# adc.net
KiCad netlist of a schematic drawn in Altium Designer
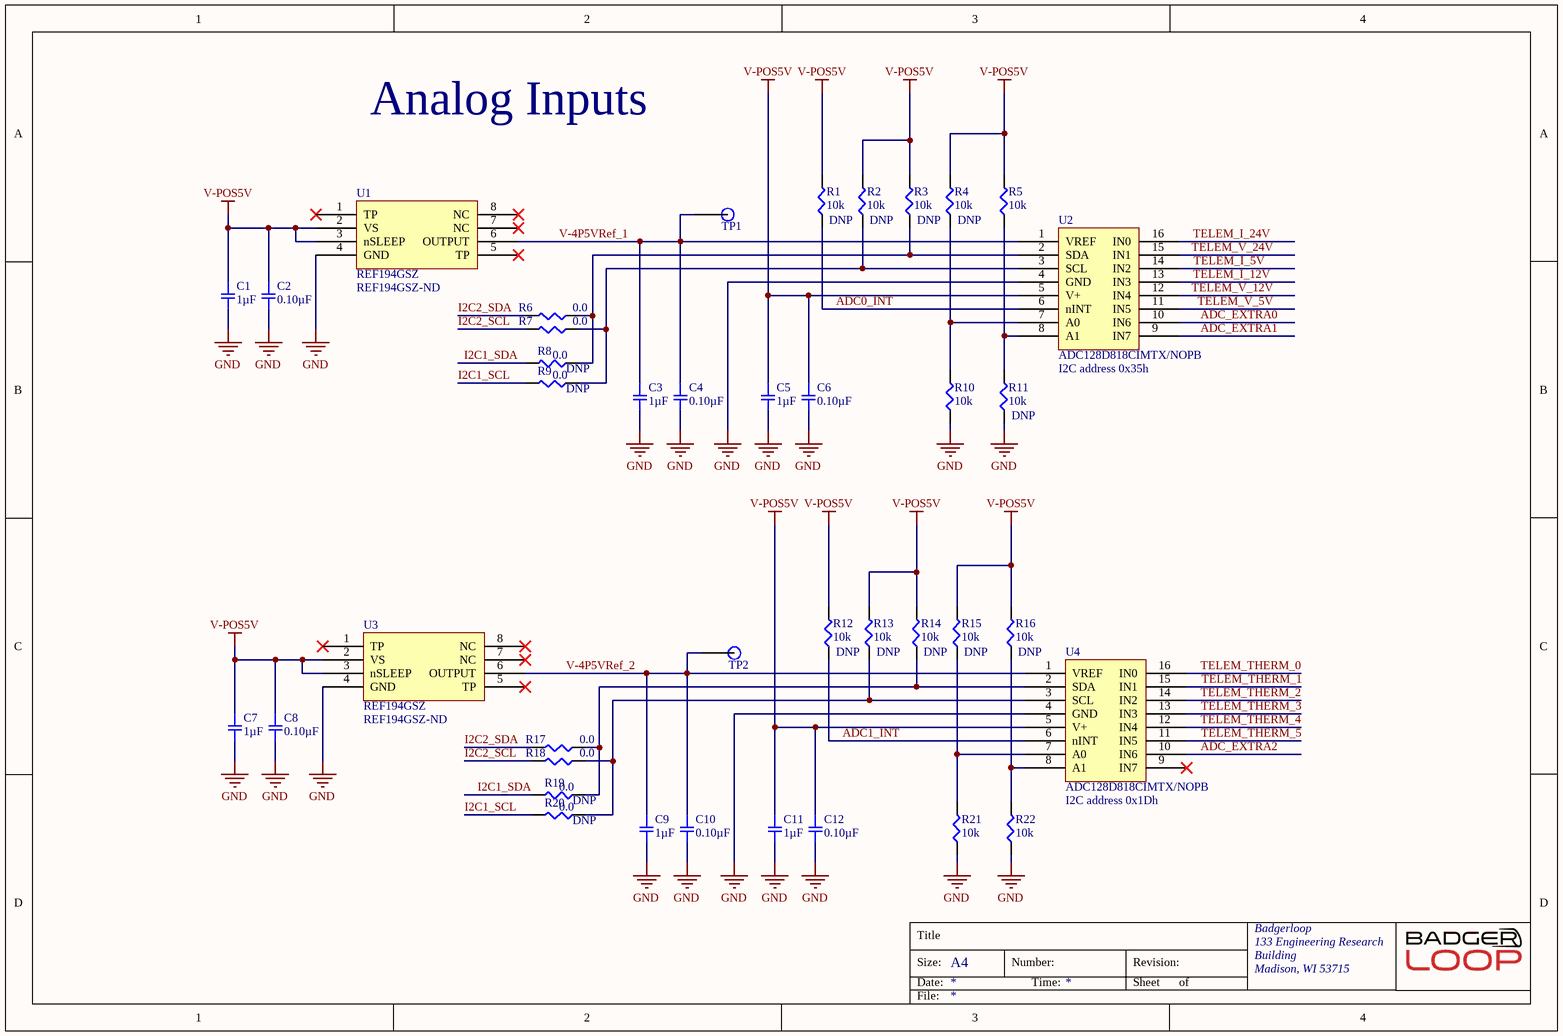
[diagram p0: adc.SchDoc]

(export (version "E")
  (design (tool "Eeschema 10.0.6"))
  (components
    (comp (ref "C1")
      (value "1µF")
      (footprint "SMD-0805C")
      (description "CAP CER 1UF 50V X7R 0805")
      (fields
        (field (name "DIGI-KEY PART NUMBER") "490-4736-1-ND")
        (field (name "PART NUMBER") "GRM21BR71H105KA12L")
      )
      (libsource (lib "capacitors") (part "GRM21BR71H105KA12L"))
    )
    (comp (ref "C2")
      (value "0.10µF")
      (footprint "SMD-0805C")
      (description "CAP CER 0.1UF 50V X7R 0805")
      (fields
        (field (name "DIGI-KEY PART NUMBER") "490-11955-1-ND")
        (field (name "PART NUMBER") "GCD21BR71H104KA01L")
      )
      (libsource (lib "capacitors") (part "GCD21BR71H104KA01L"))
    )
    (comp (ref "C3")
      (value "1µF")
      (footprint "SMD-0805C")
      (description "CAP CER 1UF 50V X7R 0805")
      (fields
        (field (name "DIGI-KEY PART NUMBER") "490-4736-1-ND")
        (field (name "PART NUMBER") "GRM21BR71H105KA12L")
      )
      (libsource (lib "capacitors") (part "GRM21BR71H105KA12L"))
    )
    (comp (ref "C4")
      (value "0.10µF")
      (footprint "SMD-0805C")
      (description "CAP CER 0.1UF 50V X7R 0805")
      (fields
        (field (name "DIGI-KEY PART NUMBER") "490-11955-1-ND")
        (field (name "PART NUMBER") "GCD21BR71H104KA01L")
      )
      (libsource (lib "capacitors") (part "GCD21BR71H104KA01L"))
    )
    (comp (ref "C5")
      (value "1µF")
      (footprint "SMD-0805C")
      (description "CAP CER 1UF 50V X7R 0805")
      (fields
        (field (name "DIGI-KEY PART NUMBER") "490-4736-1-ND")
        (field (name "PART NUMBER") "GRM21BR71H105KA12L")
      )
      (libsource (lib "capacitors") (part "GRM21BR71H105KA12L"))
    )
    (comp (ref "C6")
      (value "0.10µF")
      (footprint "SMD-0805C")
      (description "CAP CER 0.1UF 50V X7R 0805")
      (fields
        (field (name "DIGI-KEY PART NUMBER") "490-11955-1-ND")
        (field (name "PART NUMBER") "GCD21BR71H104KA01L")
      )
      (libsource (lib "capacitors") (part "GCD21BR71H104KA01L"))
    )
    (comp (ref "C7")
      (value "1µF")
      (footprint "SMD-0805C")
      (description "CAP CER 1UF 50V X7R 0805")
      (fields
        (field (name "DIGI-KEY PART NUMBER") "490-4736-1-ND")
        (field (name "PART NUMBER") "GRM21BR71H105KA12L")
      )
      (libsource (lib "capacitors") (part "GRM21BR71H105KA12L"))
    )
    (comp (ref "C8")
      (value "0.10µF")
      (footprint "SMD-0805C")
      (description "CAP CER 0.1UF 50V X7R 0805")
      (fields
        (field (name "DIGI-KEY PART NUMBER") "490-11955-1-ND")
        (field (name "PART NUMBER") "GCD21BR71H104KA01L")
      )
      (libsource (lib "capacitors") (part "GCD21BR71H104KA01L"))
    )
    (comp (ref "C9")
      (value "1µF")
      (footprint "SMD-0805C")
      (description "CAP CER 1UF 50V X7R 0805")
      (fields
        (field (name "DIGI-KEY PART NUMBER") "490-4736-1-ND")
        (field (name "PART NUMBER") "GRM21BR71H105KA12L")
      )
      (libsource (lib "capacitors") (part "GRM21BR71H105KA12L"))
    )
    (comp (ref "C10")
      (value "0.10µF")
      (footprint "SMD-0805C")
      (description "CAP CER 0.1UF 50V X7R 0805")
      (fields
        (field (name "DIGI-KEY PART NUMBER") "490-11955-1-ND")
        (field (name "PART NUMBER") "GCD21BR71H104KA01L")
      )
      (libsource (lib "capacitors") (part "GCD21BR71H104KA01L"))
    )
    (comp (ref "C11")
      (value "1µF")
      (footprint "SMD-0805C")
      (description "CAP CER 1UF 50V X7R 0805")
      (fields
        (field (name "DIGI-KEY PART NUMBER") "490-4736-1-ND")
        (field (name "PART NUMBER") "GRM21BR71H105KA12L")
      )
      (libsource (lib "capacitors") (part "GRM21BR71H105KA12L"))
    )
    (comp (ref "C12")
      (value "0.10µF")
      (footprint "SMD-0805C")
      (description "CAP CER 0.1UF 50V X7R 0805")
      (fields
        (field (name "DIGI-KEY PART NUMBER") "490-11955-1-ND")
        (field (name "PART NUMBER") "GCD21BR71H104KA01L")
      )
      (libsource (lib "capacitors") (part "GCD21BR71H104KA01L"))
    )
    (comp (ref "R1")
      (value "10k")
      (footprint "SMD-0805-RES")
      (description "RES SMD 10K OHM 5% 1/2W 0805")
      (fields
        (field (name "PART NUMBER") "ERJ-P06J103V")
        (field (name "DIGI-KEY PART NUMBER") "P10KADCT-ND")
        (field (name "DNP") "DNP")
      )
      (libsource (lib "resistors") (part "ERJ-P06J103V"))
    )
    (comp (ref "R2")
      (value "10k")
      (footprint "SMD-0805-RES")
      (description "RES SMD 10K OHM 5% 1/2W 0805")
      (fields
        (field (name "PART NUMBER") "ERJ-P06J103V")
        (field (name "DIGI-KEY PART NUMBER") "P10KADCT-ND")
        (field (name "DNP") "DNP")
      )
      (libsource (lib "resistors") (part "ERJ-P06J103V"))
    )
    (comp (ref "R3")
      (value "10k")
      (footprint "SMD-0805-RES")
      (description "RES SMD 10K OHM 5% 1/2W 0805")
      (fields
        (field (name "PART NUMBER") "ERJ-P06J103V")
        (field (name "DIGI-KEY PART NUMBER") "P10KADCT-ND")
        (field (name "DNP") "DNP")
      )
      (libsource (lib "resistors") (part "ERJ-P06J103V"))
    )
    (comp (ref "R4")
      (value "10k")
      (footprint "SMD-0805-RES")
      (description "RES SMD 10K OHM 5% 1/2W 0805")
      (fields
        (field (name "PART NUMBER") "ERJ-P06J103V")
        (field (name "DIGI-KEY PART NUMBER") "P10KADCT-ND")
        (field (name "DNP") "DNP")
      )
      (libsource (lib "resistors") (part "ERJ-P06J103V"))
    )
    (comp (ref "R5")
      (value "10k")
      (footprint "SMD-0805-RES")
      (description "RES SMD 10K OHM 5% 1/2W 0805")
      (fields (field (name "PART NUMBER") "ERJ-P06J103V") (field (name "DIGI-KEY PART NUMBER") "P10KADCT-ND"))
      (libsource (lib "resistors") (part "ERJ-P06J103V"))
    )
    (comp (ref "R6")
      (value "0.0")
      (footprint "SMD-0805-RES")
      (description "RES SMD 0.0 OHM JUMPER 1/8W 0805")
      (fields (field (name "PART NUMBER") "ERJ-6GEY0R00V") (field (name "DIGI-KEY PART NUMBER") "P0.0ACT-ND"))
      (libsource (lib "resistors") (part "ERJ-6GEY0R00V"))
    )
    (comp (ref "R7")
      (value "0.0")
      (footprint "SMD-0805-RES")
      (description "RES SMD 0.0 OHM JUMPER 1/8W 0805")
      (fields (field (name "PART NUMBER") "ERJ-6GEY0R00V") (field (name "DIGI-KEY PART NUMBER") "P0.0ACT-ND"))
      (libsource (lib "resistors") (part "ERJ-6GEY0R00V"))
    )
    (comp (ref "R8")
      (value "0.0")
      (footprint "SMD-0805-RES")
      (description "RES SMD 0.0 OHM JUMPER 1/8W 0805")
      (fields
        (field (name "PART NUMBER") "ERJ-6GEY0R00V")
        (field (name "DIGI-KEY PART NUMBER") "P0.0ACT-ND")
        (field (name "DNP") "DNP")
      )
      (libsource (lib "resistors") (part "ERJ-6GEY0R00V"))
    )
    (comp (ref "R9")
      (value "0.0")
      (footprint "SMD-0805-RES")
      (description "RES SMD 0.0 OHM JUMPER 1/8W 0805")
      (fields
        (field (name "PART NUMBER") "ERJ-6GEY0R00V")
        (field (name "DIGI-KEY PART NUMBER") "P0.0ACT-ND")
        (field (name "DNP") "DNP")
      )
      (libsource (lib "resistors") (part "ERJ-6GEY0R00V"))
    )
    (comp (ref "R10")
      (value "10k")
      (footprint "SMD-0805-RES")
      (description "RES SMD 10K OHM 5% 1/2W 0805")
      (fields (field (name "PART NUMBER") "ERJ-P06J103V") (field (name "DIGI-KEY PART NUMBER") "P10KADCT-ND"))
      (libsource (lib "resistors") (part "ERJ-P06J103V"))
    )
    (comp (ref "R11")
      (value "10k")
      (footprint "SMD-0805-RES")
      (description "RES SMD 10K OHM 5% 1/2W 0805")
      (fields
        (field (name "PART NUMBER") "ERJ-P06J103V")
        (field (name "DIGI-KEY PART NUMBER") "P10KADCT-ND")
        (field (name "DNP") "DNP")
      )
      (libsource (lib "resistors") (part "ERJ-P06J103V"))
    )
    (comp (ref "R12")
      (value "10k")
      (footprint "SMD-0805-RES")
      (description "RES SMD 10K OHM 5% 1/2W 0805")
      (fields
        (field (name "PART NUMBER") "ERJ-P06J103V")
        (field (name "DIGI-KEY PART NUMBER") "P10KADCT-ND")
        (field (name "DNP") "DNP")
      )
      (libsource (lib "resistors") (part "ERJ-P06J103V"))
    )
    (comp (ref "R13")
      (value "10k")
      (footprint "SMD-0805-RES")
      (description "RES SMD 10K OHM 5% 1/2W 0805")
      (fields
        (field (name "PART NUMBER") "ERJ-P06J103V")
        (field (name "DIGI-KEY PART NUMBER") "P10KADCT-ND")
        (field (name "DNP") "DNP")
      )
      (libsource (lib "resistors") (part "ERJ-P06J103V"))
    )
    (comp (ref "R14")
      (value "10k")
      (footprint "SMD-0805-RES")
      (description "RES SMD 10K OHM 5% 1/2W 0805")
      (fields
        (field (name "PART NUMBER") "ERJ-P06J103V")
        (field (name "DIGI-KEY PART NUMBER") "P10KADCT-ND")
        (field (name "DNP") "DNP")
      )
      (libsource (lib "resistors") (part "ERJ-P06J103V"))
    )
    (comp (ref "R15")
      (value "10k")
      (footprint "SMD-0805-RES")
      (description "RES SMD 10K OHM 5% 1/2W 0805")
      (fields
        (field (name "PART NUMBER") "ERJ-P06J103V")
        (field (name "DIGI-KEY PART NUMBER") "P10KADCT-ND")
        (field (name "DNP") "DNP")
      )
      (libsource (lib "resistors") (part "ERJ-P06J103V"))
    )
    (comp (ref "R16")
      (value "10k")
      (footprint "SMD-0805-RES")
      (description "RES SMD 10K OHM 5% 1/2W 0805")
      (fields
        (field (name "PART NUMBER") "ERJ-P06J103V")
        (field (name "DIGI-KEY PART NUMBER") "P10KADCT-ND")
        (field (name "DNP") "DNP")
      )
      (libsource (lib "resistors") (part "ERJ-P06J103V"))
    )
    (comp (ref "R17")
      (value "0.0")
      (footprint "SMD-0805-RES")
      (description "RES SMD 0.0 OHM JUMPER 1/8W 0805")
      (fields (field (name "PART NUMBER") "ERJ-6GEY0R00V") (field (name "DIGI-KEY PART NUMBER") "P0.0ACT-ND"))
      (libsource (lib "resistors") (part "ERJ-6GEY0R00V"))
    )
    (comp (ref "R18")
      (value "0.0")
      (footprint "SMD-0805-RES")
      (description "RES SMD 0.0 OHM JUMPER 1/8W 0805")
      (fields (field (name "PART NUMBER") "ERJ-6GEY0R00V") (field (name "DIGI-KEY PART NUMBER") "P0.0ACT-ND"))
      (libsource (lib "resistors") (part "ERJ-6GEY0R00V"))
    )
    (comp (ref "R19")
      (value "0.0")
      (footprint "SMD-0805-RES")
      (description "RES SMD 0.0 OHM JUMPER 1/8W 0805")
      (fields
        (field (name "PART NUMBER") "ERJ-6GEY0R00V")
        (field (name "DIGI-KEY PART NUMBER") "P0.0ACT-ND")
        (field (name "DNP") "DNP")
      )
      (libsource (lib "resistors") (part "ERJ-6GEY0R00V"))
    )
    (comp (ref "R20")
      (value "0.0")
      (footprint "SMD-0805-RES")
      (description "RES SMD 0.0 OHM JUMPER 1/8W 0805")
      (fields
        (field (name "PART NUMBER") "ERJ-6GEY0R00V")
        (field (name "DIGI-KEY PART NUMBER") "P0.0ACT-ND")
        (field (name "DNP") "DNP")
      )
      (libsource (lib "resistors") (part "ERJ-6GEY0R00V"))
    )
    (comp (ref "R21")
      (value "10k")
      (footprint "SMD-0805-RES")
      (description "RES SMD 10K OHM 5% 1/2W 0805")
      (fields (field (name "PART NUMBER") "ERJ-P06J103V") (field (name "DIGI-KEY PART NUMBER") "P10KADCT-ND"))
      (libsource (lib "resistors") (part "ERJ-P06J103V"))
    )
    (comp (ref "R22")
      (value "10k")
      (footprint "SMD-0805-RES")
      (description "RES SMD 10K OHM 5% 1/2W 0805")
      (fields (field (name "PART NUMBER") "ERJ-P06J103V") (field (name "DIGI-KEY PART NUMBER") "P10KADCT-ND"))
      (libsource (lib "resistors") (part "ERJ-P06J103V"))
    )
    (comp (ref "TP1")
      (value "TP")
      (footprint "Test Point")
      (description "SMD TEST POINT")
      (libsource (lib "misc") (part "TP"))
    )
    (comp (ref "TP2")
      (value "TP")
      (footprint "Test Point")
      (description "SMD TEST POINT")
      (libsource (lib "misc") (part "TP"))
    )
    (comp (ref "U1")
      (value "REF194GSZ")
      (footprint "SOP127P600X175-8N")
      (description "IC VREF SERIES 4.5V 8SOIC")
      (fields
        (field (name "MANUFACTURER") "Analog Devices")
        (field (name "SUPPLIER PART NUMBER 1") "REF194GSZ-ND")
      )
      (libsource (lib "ic") (part "REF194GSZ"))
    )
    (comp (ref "U2")
      (value "ADC128D818CIMTX/NOPB")
      (footprint "TSOP65P660X120-16N")
      (description "Analog to Digital Converters - ADC")
      (fields (field (name "MANUFACTURER") "TI National Semiconductor"))
      (libsource (lib "ic") (part "ADC128D818CIMTX/NOPB"))
    )
    (comp (ref "U3")
      (value "REF194GSZ")
      (footprint "SOP127P600X175-8N")
      (description "IC VREF SERIES 4.5V 8SOIC")
      (fields
        (field (name "MANUFACTURER") "Analog Devices")
        (field (name "SUPPLIER PART NUMBER 1") "REF194GSZ-ND")
      )
      (libsource (lib "ic") (part "REF194GSZ"))
    )
    (comp (ref "U4")
      (value "ADC128D818CIMTX/NOPB")
      (footprint "TSOP65P660X120-16N")
      (description "Analog to Digital Converters - ADC")
      (fields (field (name "MANUFACTURER") "TI National Semiconductor"))
      (libsource (lib "ic") (part "ADC128D818CIMTX/NOPB"))
    )
  )
  (nets
    (net (code "1") (name "/ADC0_INT") (class "Default")
      (node (ref "R1") (pin "1") (pinfunction "1_1") (pintype "passive"))
      (node (ref "U2") (pin "6") (pinfunction "nINT_6") (pintype "passive"))
    )
    (net (code "2") (name "/ADC1_INT") (class "Default")
      (node (ref "R12") (pin "1") (pinfunction "1_1") (pintype "passive"))
      (node (ref "U4") (pin "6") (pinfunction "nINT_6") (pintype "passive"))
    )
    (net (code "3") (name "/ADC_EXTRA0") (class "Default")
      (node (ref "U2") (pin "10") (pinfunction "IN6_10") (pintype "passive"))
    )
    (net (code "4") (name "/ADC_EXTRA1") (class "Default")
      (node (ref "U2") (pin "9") (pinfunction "IN7_9") (pintype "passive"))
    )
    (net (code "5") (name "/ADC_EXTRA2") (class "Default")
      (node (ref "U4") (pin "10") (pinfunction "IN6_10") (pintype "passive"))
    )
    (net (code "6") (name "/I2C1_SCL") (class "Default")
      (node (ref "R20") (pin "2") (pinfunction "2_2") (pintype "passive"))
      (node (ref "R9") (pin "2") (pinfunction "2_2") (pintype "passive"))
    )
    (net (code "7") (name "/I2C1_SDA") (class "Default")
      (node (ref "R19") (pin "2") (pinfunction "2_2") (pintype "passive"))
      (node (ref "R8") (pin "2") (pinfunction "2_2") (pintype "passive"))
    )
    (net (code "8") (name "/I2C2_SCL") (class "Default")
      (node (ref "R18") (pin "2") (pinfunction "2_2") (pintype "passive"))
      (node (ref "R7") (pin "2") (pinfunction "2_2") (pintype "passive"))
    )
    (net (code "9") (name "/I2C2_SDA") (class "Default")
      (node (ref "R17") (pin "2") (pinfunction "2_2") (pintype "passive"))
      (node (ref "R6") (pin "2") (pinfunction "2_2") (pintype "passive"))
    )
    (net (code "10") (name "/TELEM_I_5V") (class "Default")
      (node (ref "U2") (pin "14") (pinfunction "IN2_14") (pintype "passive"))
    )
    (net (code "11") (name "/TELEM_I_12V") (class "Default")
      (node (ref "U2") (pin "13") (pinfunction "IN3_13") (pintype "passive"))
    )
    (net (code "12") (name "/TELEM_I_24V") (class "Default")
      (node (ref "U2") (pin "16") (pinfunction "IN0_16") (pintype "passive"))
    )
    (net (code "13") (name "/TELEM_THERM_0") (class "Default")
      (node (ref "U4") (pin "16") (pinfunction "IN0_16") (pintype "passive"))
    )
    (net (code "14") (name "/TELEM_THERM_1") (class "Default")
      (node (ref "U4") (pin "15") (pinfunction "IN1_15") (pintype "passive"))
    )
    (net (code "15") (name "/TELEM_THERM_2") (class "Default")
      (node (ref "U4") (pin "14") (pinfunction "IN2_14") (pintype "passive"))
    )
    (net (code "16") (name "/TELEM_THERM_3") (class "Default")
      (node (ref "U4") (pin "13") (pinfunction "IN3_13") (pintype "passive"))
    )
    (net (code "17") (name "/TELEM_THERM_4") (class "Default")
      (node (ref "U4") (pin "12") (pinfunction "IN4_12") (pintype "passive"))
    )
    (net (code "18") (name "/TELEM_THERM_5") (class "Default")
      (node (ref "U4") (pin "11") (pinfunction "IN5_11") (pintype "passive"))
    )
    (net (code "19") (name "/TELEM_V_5V") (class "Default")
      (node (ref "U2") (pin "11") (pinfunction "IN5_11") (pintype "passive"))
    )
    (net (code "20") (name "/TELEM_V_12V") (class "Default")
      (node (ref "U2") (pin "12") (pinfunction "IN4_12") (pintype "passive"))
    )
    (net (code "21") (name "/TELEM_V_24V") (class "Default")
      (node (ref "U2") (pin "15") (pinfunction "IN1_15") (pintype "passive"))
    )
    (net (code "22") (name "/V-4P5VRef_1") (class "Default")
      (node (ref "C3") (pin "1") (pinfunction "1_1") (pintype "passive"))
      (node (ref "C4") (pin "1") (pinfunction "1_1") (pintype "passive"))
      (node (ref "TP1") (pin "1") (pinfunction "1_1") (pintype "passive"))
      (node (ref "U1") (pin "6") (pinfunction "OUTPUT_6") (pintype "passive"))
      (node (ref "U2") (pin "1") (pinfunction "VREF_1") (pintype "passive"))
    )
    (net (code "23") (name "/V-4P5VRef_2") (class "Default")
      (node (ref "C10") (pin "1") (pinfunction "1_1") (pintype "passive"))
      (node (ref "C9") (pin "1") (pinfunction "1_1") (pintype "passive"))
      (node (ref "TP2") (pin "1") (pinfunction "1_1") (pintype "passive"))
      (node (ref "U3") (pin "6") (pinfunction "OUTPUT_6") (pintype "passive"))
      (node (ref "U4") (pin "1") (pinfunction "VREF_1") (pintype "passive"))
    )
    (net (code "24") (name "GND") (class "Default")
      (node (ref "C1") (pin "2") (pinfunction "2_2") (pintype "passive"))
      (node (ref "C10") (pin "2") (pinfunction "2_2") (pintype "passive"))
      (node (ref "C11") (pin "2") (pinfunction "2_2") (pintype "passive"))
      (node (ref "C12") (pin "2") (pinfunction "2_2") (pintype "passive"))
      (node (ref "C2") (pin "2") (pinfunction "2_2") (pintype "passive"))
      (node (ref "C3") (pin "2") (pinfunction "2_2") (pintype "passive"))
      (node (ref "C4") (pin "2") (pinfunction "2_2") (pintype "passive"))
      (node (ref "C5") (pin "2") (pinfunction "2_2") (pintype "passive"))
      (node (ref "C6") (pin "2") (pinfunction "2_2") (pintype "passive"))
      (node (ref "C7") (pin "2") (pinfunction "2_2") (pintype "passive"))
      (node (ref "C8") (pin "2") (pinfunction "2_2") (pintype "passive"))
      (node (ref "C9") (pin "2") (pinfunction "2_2") (pintype "passive"))
      (node (ref "R10") (pin "1") (pinfunction "1_1") (pintype "passive"))
      (node (ref "R11") (pin "1") (pinfunction "1_1") (pintype "passive"))
      (node (ref "R21") (pin "1") (pinfunction "1_1") (pintype "passive"))
      (node (ref "R22") (pin "1") (pinfunction "1_1") (pintype "passive"))
      (node (ref "U1") (pin "4") (pinfunction "GND_4") (pintype "passive"))
      (node (ref "U2") (pin "4") (pinfunction "GND_4") (pintype "passive"))
      (node (ref "U3") (pin "4") (pinfunction "GND_4") (pintype "passive"))
      (node (ref "U4") (pin "4") (pinfunction "GND_4") (pintype "passive"))
    )
    (net (code "25") (name "Net-(U2-A0)") (class "Default")
      (node (ref "R10") (pin "2") (pinfunction "2_2") (pintype "passive"))
      (node (ref "R4") (pin "1") (pinfunction "1_1") (pintype "passive"))
      (node (ref "U2") (pin "7") (pinfunction "A0_7") (pintype "passive"))
    )
    (net (code "26") (name "Net-(U2-A1)") (class "Default")
      (node (ref "R11") (pin "2") (pinfunction "2_2") (pintype "passive"))
      (node (ref "R5") (pin "1") (pinfunction "1_1") (pintype "passive"))
      (node (ref "U2") (pin "8") (pinfunction "A1_8") (pintype "passive"))
    )
    (net (code "27") (name "Net-(U2-SCL)") (class "Default")
      (node (ref "R2") (pin "1") (pinfunction "1_1") (pintype "passive"))
      (node (ref "R7") (pin "1") (pinfunction "1_1") (pintype "passive"))
      (node (ref "R9") (pin "1") (pinfunction "1_1") (pintype "passive"))
      (node (ref "U2") (pin "3") (pinfunction "SCL_3") (pintype "passive"))
    )
    (net (code "28") (name "Net-(U2-SDA)") (class "Default")
      (node (ref "R3") (pin "1") (pinfunction "1_1") (pintype "passive"))
      (node (ref "R6") (pin "1") (pinfunction "1_1") (pintype "passive"))
      (node (ref "R8") (pin "1") (pinfunction "1_1") (pintype "passive"))
      (node (ref "U2") (pin "2") (pinfunction "SDA_2") (pintype "passive"))
    )
    (net (code "29") (name "Net-(U4-A0)") (class "Default")
      (node (ref "R15") (pin "1") (pinfunction "1_1") (pintype "passive"))
      (node (ref "R21") (pin "2") (pinfunction "2_2") (pintype "passive"))
      (node (ref "U4") (pin "7") (pinfunction "A0_7") (pintype "passive"))
    )
    (net (code "30") (name "Net-(U4-A1)") (class "Default")
      (node (ref "R16") (pin "1") (pinfunction "1_1") (pintype "passive"))
      (node (ref "R22") (pin "2") (pinfunction "2_2") (pintype "passive"))
      (node (ref "U4") (pin "8") (pinfunction "A1_8") (pintype "passive"))
    )
    (net (code "31") (name "Net-(U4-SCL)") (class "Default")
      (node (ref "R13") (pin "1") (pinfunction "1_1") (pintype "passive"))
      (node (ref "R18") (pin "1") (pinfunction "1_1") (pintype "passive"))
      (node (ref "R20") (pin "1") (pinfunction "1_1") (pintype "passive"))
      (node (ref "U4") (pin "3") (pinfunction "SCL_3") (pintype "passive"))
    )
    (net (code "32") (name "Net-(U4-SDA)") (class "Default")
      (node (ref "R14") (pin "1") (pinfunction "1_1") (pintype "passive"))
      (node (ref "R17") (pin "1") (pinfunction "1_1") (pintype "passive"))
      (node (ref "R19") (pin "1") (pinfunction "1_1") (pintype "passive"))
      (node (ref "U4") (pin "2") (pinfunction "SDA_2") (pintype "passive"))
    )
    (net (code "33") (name "V-POS5V") (class "Default")
      (node (ref "C1") (pin "1") (pinfunction "1_1") (pintype "passive"))
      (node (ref "C11") (pin "1") (pinfunction "1_1") (pintype "passive"))
      (node (ref "C12") (pin "1") (pinfunction "1_1") (pintype "passive"))
      (node (ref "C2") (pin "1") (pinfunction "1_1") (pintype "passive"))
      (node (ref "C5") (pin "1") (pinfunction "1_1") (pintype "passive"))
      (node (ref "C6") (pin "1") (pinfunction "1_1") (pintype "passive"))
      (node (ref "C7") (pin "1") (pinfunction "1_1") (pintype "passive"))
      (node (ref "C8") (pin "1") (pinfunction "1_1") (pintype "passive"))
      (node (ref "R1") (pin "2") (pinfunction "2_2") (pintype "passive"))
      (node (ref "R12") (pin "2") (pinfunction "2_2") (pintype "passive"))
      (node (ref "R13") (pin "2") (pinfunction "2_2") (pintype "passive"))
      (node (ref "R14") (pin "2") (pinfunction "2_2") (pintype "passive"))
      (node (ref "R15") (pin "2") (pinfunction "2_2") (pintype "passive"))
      (node (ref "R16") (pin "2") (pinfunction "2_2") (pintype "passive"))
      (node (ref "R2") (pin "2") (pinfunction "2_2") (pintype "passive"))
      (node (ref "R3") (pin "2") (pinfunction "2_2") (pintype "passive"))
      (node (ref "R4") (pin "2") (pinfunction "2_2") (pintype "passive"))
      (node (ref "R5") (pin "2") (pinfunction "2_2") (pintype "passive"))
      (node (ref "U1") (pin "2") (pinfunction "VS_2") (pintype "passive"))
      (node (ref "U1") (pin "3") (pinfunction "nSLEEP_3") (pintype "passive"))
      (node (ref "U2") (pin "5") (pinfunction "V+_5") (pintype "passive"))
      (node (ref "U3") (pin "2") (pinfunction "VS_2") (pintype "passive"))
      (node (ref "U3") (pin "3") (pinfunction "nSLEEP_3") (pintype "passive"))
      (node (ref "U4") (pin "5") (pinfunction "V+_5") (pintype "passive"))
    )
    (net (code "34") (name "unconnected-(U1-NC-Pad7)") (class "Default")
      (node (ref "U1") (pin "7") (pinfunction "NC_7") (pintype "passive+no_connect"))
    )
    (net (code "35") (name "unconnected-(U1-NC-Pad8)") (class "Default")
      (node (ref "U1") (pin "8") (pinfunction "NC_8") (pintype "passive+no_connect"))
    )
    (net (code "36") (name "unconnected-(U1-TP-Pad1)") (class "Default")
      (node (ref "U1") (pin "1") (pinfunction "TP_1") (pintype "passive+no_connect"))
    )
    (net (code "37") (name "unconnected-(U1-TP-Pad5)") (class "Default")
      (node (ref "U1") (pin "5") (pinfunction "TP_5") (pintype "passive+no_connect"))
    )
    (net (code "38") (name "unconnected-(U3-NC-Pad7)") (class "Default")
      (node (ref "U3") (pin "7") (pinfunction "NC_7") (pintype "passive+no_connect"))
    )
    (net (code "39") (name "unconnected-(U3-NC-Pad8)") (class "Default")
      (node (ref "U3") (pin "8") (pinfunction "NC_8") (pintype "passive+no_connect"))
    )
    (net (code "40") (name "unconnected-(U3-TP-Pad1)") (class "Default")
      (node (ref "U3") (pin "1") (pinfunction "TP_1") (pintype "passive+no_connect"))
    )
    (net (code "41") (name "unconnected-(U3-TP-Pad5)") (class "Default")
      (node (ref "U3") (pin "5") (pinfunction "TP_5") (pintype "passive+no_connect"))
    )
    (net (code "42") (name "unconnected-(U4-IN7-Pad9)") (class "Default")
      (node (ref "U4") (pin "9") (pinfunction "IN7_9") (pintype "passive+no_connect"))
    )
  )
)
